# Enclosure_85x58_WS.net
KiCad netlist of a schematic drawn in EAGLE
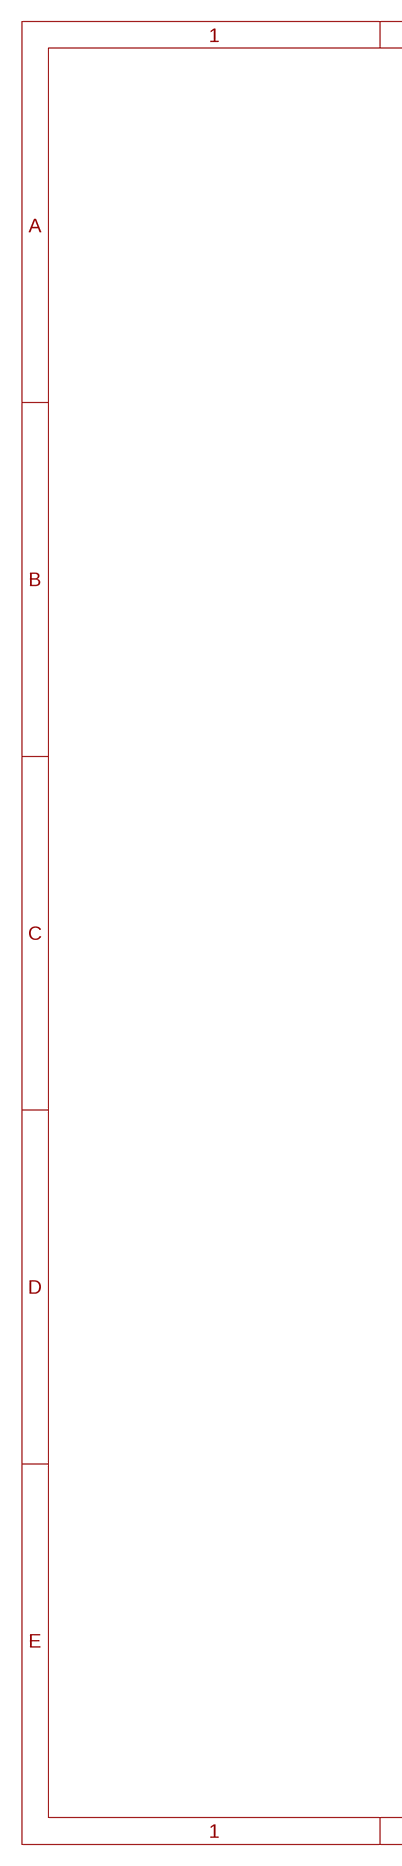
[diagram p0: schematic, sheet 1, part 1 of 2]
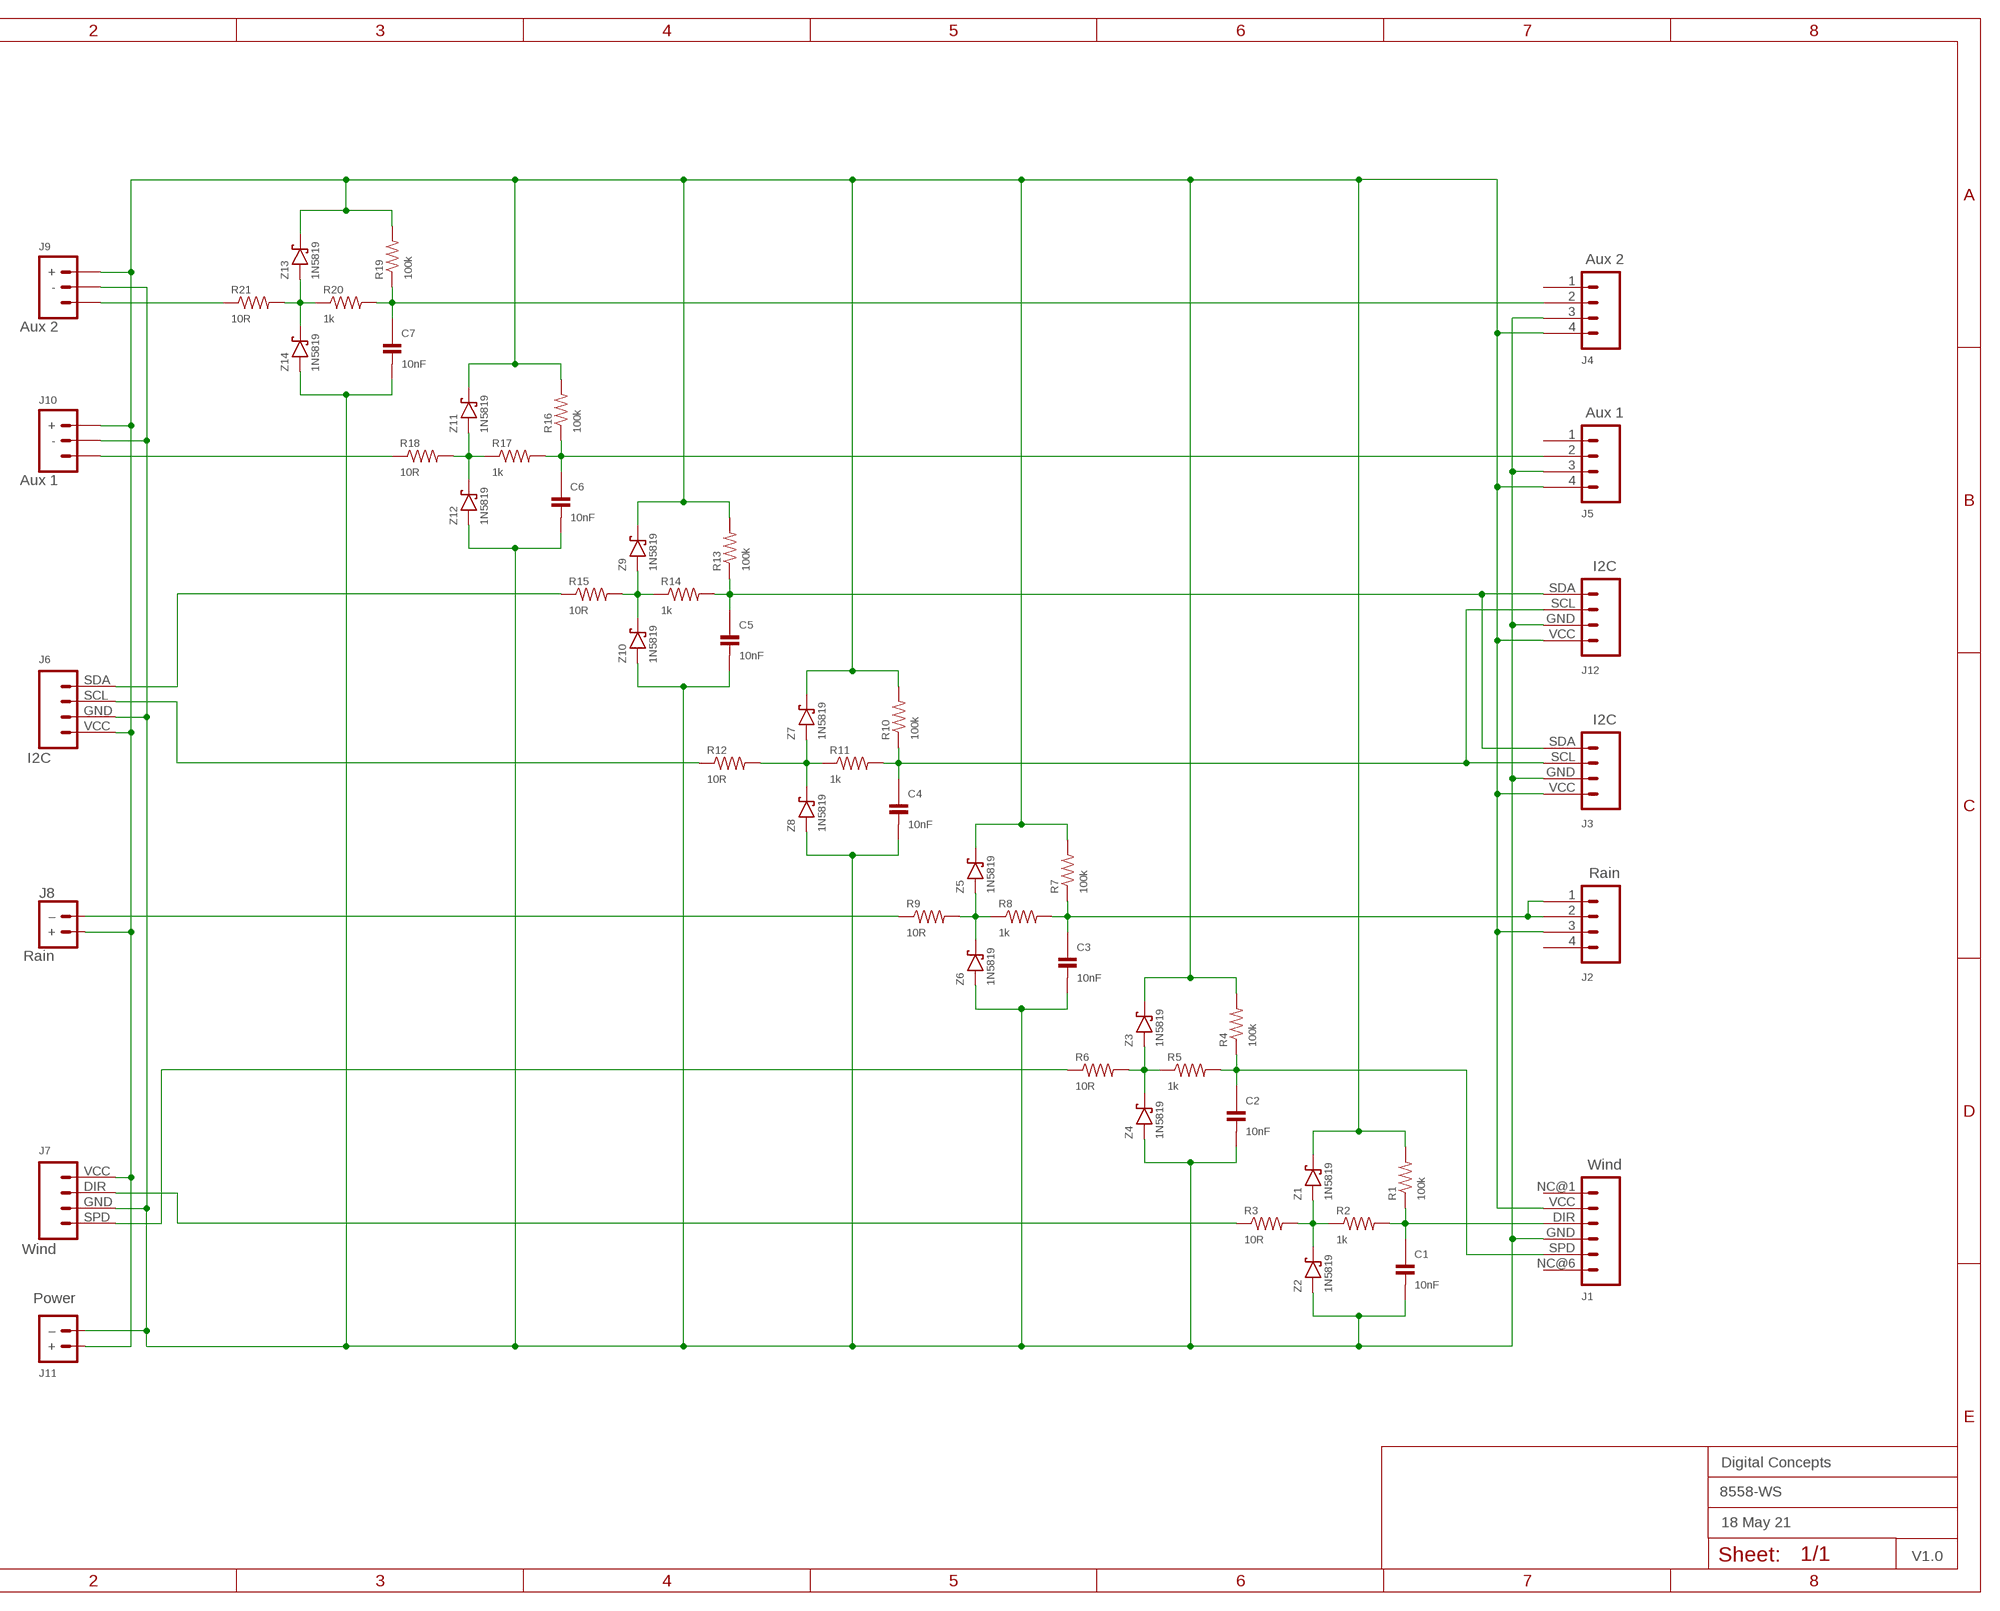
[diagram p1: schematic, sheet 1, part 2 of 2]

(export (version "E")
  (design (tool "Eeschema 10.0.6"))
  (components
    (comp (ref "C1")
      (value "10nF")
      (footprint "eagle-import:C0805-VIA-2")
      (libsource (lib "eagle-import") (part "CAPACITOR-0805-VIA-2"))
    )
    (comp (ref "C2")
      (value "10nF")
      (footprint "eagle-import:C0805-VIA-2")
      (libsource (lib "eagle-import") (part "CAPACITOR-0805-VIA-2"))
    )
    (comp (ref "C3")
      (value "10nF")
      (footprint "eagle-import:C0805-VIA-2")
      (libsource (lib "eagle-import") (part "CAPACITOR-0805-VIA-2"))
    )
    (comp (ref "C4")
      (value "10nF")
      (footprint "eagle-import:C0805-VIA-2")
      (libsource (lib "eagle-import") (part "CAPACITOR-0805-VIA-2"))
    )
    (comp (ref "C5")
      (value "10nF")
      (footprint "eagle-import:C0805-VIA-2")
      (libsource (lib "eagle-import") (part "CAPACITOR-0805-VIA-2"))
    )
    (comp (ref "C6")
      (value "10nF")
      (footprint "eagle-import:C0805-VIA-2")
      (libsource (lib "eagle-import") (part "CAPACITOR-0805-VIA-2"))
    )
    (comp (ref "C7")
      (value "10nF")
      (footprint "eagle-import:C0805-VIA-2")
      (libsource (lib "eagle-import") (part "CAPACITOR-0805-VIA-2"))
    )
    (comp (ref "J1")
      (value "Wind")
      (footprint "eagle-import:RJ11-6-VERTICAL-WIND")
      (libsource (lib "eagle-import") (part "RJ11-6P6C-VERTICAL-WIND"))
    )
    (comp (ref "J2")
      (value "Rain")
      (footprint "eagle-import:RJ11-4-VERTICAL")
      (libsource (lib "eagle-import") (part "RJ11-6P4C-VERTICAL"))
    )
    (comp (ref "J3")
      (value "I2C")
      (footprint "eagle-import:RJ11-4-VERTICAL-I2C")
      (libsource (lib "eagle-import") (part "RJ11-6P4C-VERTICAL-I2C"))
    )
    (comp (ref "J4")
      (value "Aux 2")
      (footprint "eagle-import:RJ11-4-VERTICAL")
      (libsource (lib "eagle-import") (part "RJ11-6P4C-VERTICAL"))
    )
    (comp (ref "J5")
      (value "Aux 1")
      (footprint "eagle-import:RJ11-4-VERTICAL")
      (libsource (lib "eagle-import") (part "RJ11-6P4C-VERTICAL"))
    )
    (comp (ref "J6")
      (value "I2C")
      (footprint "eagle-import:JST-PH2.0-4-VERTICAL-I2C")
      (libsource (lib "eagle-import") (part "JST-PH2.0-4-MALE-VERTICAL-I2C"))
    )
    (comp (ref "J7")
      (value "Wind")
      (footprint "eagle-import:JST-PH2.0-4-VERTICAL-WIND")
      (libsource (lib "eagle-import") (part "JST-PH2.0-4-MALE-VERTICAL-WIND"))
    )
    (comp (ref "J8")
      (value "Rain")
      (footprint "eagle-import:JST-PH2.0-2-VERTICAL=POWER")
      (libsource (lib "eagle-import") (part "JST-PH2.0-2-MALE-VERTICAL"))
    )
    (comp (ref "J9")
      (value "Aux 2")
      (footprint "eagle-import:JST-PH2.0-3-VERTICAL")
      (libsource (lib "eagle-import") (part "JST-PH2.0-3-MALE-VERTICAL"))
    )
    (comp (ref "J10")
      (value "Aux 1")
      (footprint "eagle-import:JST-PH2.0-3-VERTICAL")
      (libsource (lib "eagle-import") (part "JST-PH2.0-3-MALE-VERTICAL"))
    )
    (comp (ref "J11")
      (value "Power")
      (footprint "eagle-import:JST-PH2.0-2-VERTICAL=POWER")
      (libsource (lib "eagle-import") (part "JST-PH2.0-2-MALE-VERTICAL"))
    )
    (comp (ref "J12")
      (value "I2C")
      (footprint "eagle-import:CONN_04-I2C")
      (libsource (lib "eagle-import") (part "HEADER-1X4-I2C"))
    )
    (comp (ref "R1")
      (value "100k")
      (footprint "eagle-import:R0805")
      (libsource (lib "eagle-import") (part "RESISTORR0805"))
    )
    (comp (ref "R2")
      (value "1k")
      (footprint "eagle-import:R0805")
      (libsource (lib "eagle-import") (part "RESISTORR0805"))
    )
    (comp (ref "R3")
      (value "10R")
      (footprint "eagle-import:R0805-VIA-1")
      (libsource (lib "eagle-import") (part "RESISTOR-VIA-1"))
    )
    (comp (ref "R4")
      (value "100k")
      (footprint "eagle-import:R0805")
      (libsource (lib "eagle-import") (part "RESISTORR0805"))
    )
    (comp (ref "R5")
      (value "1k")
      (footprint "eagle-import:R0805")
      (libsource (lib "eagle-import") (part "RESISTORR0805"))
    )
    (comp (ref "R6")
      (value "10R")
      (footprint "eagle-import:R0805-VIA-1")
      (libsource (lib "eagle-import") (part "RESISTOR-VIA-1"))
    )
    (comp (ref "R7")
      (value "100k")
      (footprint "eagle-import:R0805")
      (libsource (lib "eagle-import") (part "RESISTORR0805"))
    )
    (comp (ref "R8")
      (value "1k")
      (footprint "eagle-import:R0805")
      (libsource (lib "eagle-import") (part "RESISTORR0805"))
    )
    (comp (ref "R9")
      (value "10R")
      (footprint "eagle-import:R0805-VIA-1")
      (libsource (lib "eagle-import") (part "RESISTOR-VIA-1"))
    )
    (comp (ref "R10")
      (value "100k")
      (footprint "eagle-import:R0805")
      (libsource (lib "eagle-import") (part "RESISTORR0805"))
    )
    (comp (ref "R11")
      (value "1k")
      (footprint "eagle-import:R0805")
      (libsource (lib "eagle-import") (part "RESISTORR0805"))
    )
    (comp (ref "R12")
      (value "10R")
      (footprint "eagle-import:R0805-VIA-1")
      (libsource (lib "eagle-import") (part "RESISTOR-VIA-1"))
    )
    (comp (ref "R13")
      (value "100k")
      (footprint "eagle-import:R0805")
      (libsource (lib "eagle-import") (part "RESISTORR0805"))
    )
    (comp (ref "R14")
      (value "1k")
      (footprint "eagle-import:R0805")
      (libsource (lib "eagle-import") (part "RESISTORR0805"))
    )
    (comp (ref "R15")
      (value "10R")
      (footprint "eagle-import:R0805-VIA-1")
      (libsource (lib "eagle-import") (part "RESISTOR-VIA-1"))
    )
    (comp (ref "R16")
      (value "100k")
      (footprint "eagle-import:R0805")
      (libsource (lib "eagle-import") (part "RESISTORR0805"))
    )
    (comp (ref "R17")
      (value "1k")
      (footprint "eagle-import:R0805")
      (libsource (lib "eagle-import") (part "RESISTORR0805"))
    )
    (comp (ref "R18")
      (value "10R")
      (footprint "eagle-import:R0805-VIA-1")
      (libsource (lib "eagle-import") (part "RESISTOR-VIA-1"))
    )
    (comp (ref "R19")
      (value "100k")
      (footprint "eagle-import:R0805")
      (libsource (lib "eagle-import") (part "RESISTORR0805"))
    )
    (comp (ref "R20")
      (value "1k")
      (footprint "eagle-import:R0805")
      (libsource (lib "eagle-import") (part "RESISTORR0805"))
    )
    (comp (ref "R21")
      (value "10R")
      (footprint "eagle-import:R0805-VIA-1")
      (libsource (lib "eagle-import") (part "RESISTOR-VIA-1"))
    )
    (comp (ref "Z1")
      (value "1N5819")
      (footprint "eagle-import:SOD-123")
      (libsource (lib "eagle-import") (part "DIODE-SCHOTTKY-1N5819"))
    )
    (comp (ref "Z2")
      (value "1N5819")
      (footprint "eagle-import:SOD-123-VIA-A")
      (libsource (lib "eagle-import") (part "DIODE-SCHOTTKY-1N5819-VIA-A"))
    )
    (comp (ref "Z3")
      (value "1N5819")
      (footprint "eagle-import:SOD-123")
      (libsource (lib "eagle-import") (part "DIODE-SCHOTTKY-1N5819"))
    )
    (comp (ref "Z4")
      (value "1N5819")
      (footprint "eagle-import:SOD-123-VIA-A")
      (libsource (lib "eagle-import") (part "DIODE-SCHOTTKY-1N5819-VIA-A"))
    )
    (comp (ref "Z5")
      (value "1N5819")
      (footprint "eagle-import:SOD-123")
      (libsource (lib "eagle-import") (part "DIODE-SCHOTTKY-1N5819"))
    )
    (comp (ref "Z6")
      (value "1N5819")
      (footprint "eagle-import:SOD-123-VIA-A")
      (libsource (lib "eagle-import") (part "DIODE-SCHOTTKY-1N5819-VIA-A"))
    )
    (comp (ref "Z7")
      (value "1N5819")
      (footprint "eagle-import:SOD-123")
      (libsource (lib "eagle-import") (part "DIODE-SCHOTTKY-1N5819"))
    )
    (comp (ref "Z8")
      (value "1N5819")
      (footprint "eagle-import:SOD-123-VIA-A")
      (libsource (lib "eagle-import") (part "DIODE-SCHOTTKY-1N5819-VIA-A"))
    )
    (comp (ref "Z9")
      (value "1N5819")
      (footprint "eagle-import:SOD-123")
      (libsource (lib "eagle-import") (part "DIODE-SCHOTTKY-1N5819"))
    )
    (comp (ref "Z10")
      (value "1N5819")
      (footprint "eagle-import:SOD-123-VIA-A")
      (libsource (lib "eagle-import") (part "DIODE-SCHOTTKY-1N5819-VIA-A"))
    )
    (comp (ref "Z11")
      (value "1N5819")
      (footprint "eagle-import:SOD-123")
      (libsource (lib "eagle-import") (part "DIODE-SCHOTTKY-1N5819"))
    )
    (comp (ref "Z12")
      (value "1N5819")
      (footprint "eagle-import:SOD-123-VIA-A")
      (libsource (lib "eagle-import") (part "DIODE-SCHOTTKY-1N5819-VIA-A"))
    )
    (comp (ref "Z13")
      (value "1N5819")
      (footprint "eagle-import:SOD-123")
      (libsource (lib "eagle-import") (part "DIODE-SCHOTTKY-1N5819"))
    )
    (comp (ref "Z14")
      (value "1N5819")
      (footprint "eagle-import:SOD-123-VIA-A")
      (libsource (lib "eagle-import") (part "DIODE-SCHOTTKY-1N5819-VIA-A"))
    )
  )
  (nets
    (net (code "1") (name "Net-(J1-2)") (class "Default")
      (node (ref "J1") (pin "VCC") (pinfunction "2_VCC") (pintype "passive"))
      (node (ref "J10") (pin "+") (pinfunction "+_+") (pintype "power_in"))
      (node (ref "J11") (pin "+") (pinfunction "+_+") (pintype "power_in"))
      (node (ref "J12") (pin "VCC") (pinfunction "1_VCC") (pintype "passive"))
      (node (ref "J2") (pin "3") (pinfunction "2_3") (pintype "passive"))
      (node (ref "J3") (pin "VCC") (pinfunction "1_VCC") (pintype "passive"))
      (node (ref "J4") (pin "4") (pinfunction "1_4") (pintype "passive"))
      (node (ref "J5") (pin "4") (pinfunction "1_4") (pintype "passive"))
      (node (ref "J6") (pin "VCC") (pinfunction "4_VCC") (pintype "passive"))
      (node (ref "J7") (pin "VCC") (pinfunction "1_VCC") (pintype "passive"))
      (node (ref "J8") (pin "+") (pinfunction "+_+") (pintype "power_in"))
      (node (ref "J9") (pin "+") (pinfunction "+_+") (pintype "power_in"))
      (node (ref "R1") (pin "2") (pinfunction "2_2") (pintype "passive"))
      (node (ref "R10") (pin "2") (pinfunction "2_2") (pintype "passive"))
      (node (ref "R13") (pin "2") (pinfunction "2_2") (pintype "passive"))
      (node (ref "R16") (pin "2") (pinfunction "2_2") (pintype "passive"))
      (node (ref "R19") (pin "2") (pinfunction "2_2") (pintype "passive"))
      (node (ref "R4") (pin "2") (pinfunction "2_2") (pintype "passive"))
      (node (ref "R7") (pin "2") (pinfunction "2_2") (pintype "passive"))
      (node (ref "Z1") (pin "C") (pinfunction "C_C") (pintype "passive"))
      (node (ref "Z11") (pin "C") (pinfunction "C_C") (pintype "passive"))
      (node (ref "Z13") (pin "C") (pinfunction "C_C") (pintype "passive"))
      (node (ref "Z3") (pin "C") (pinfunction "C_C") (pintype "passive"))
      (node (ref "Z5") (pin "C") (pinfunction "C_C") (pintype "passive"))
      (node (ref "Z7") (pin "C") (pinfunction "C_C") (pintype "passive"))
      (node (ref "Z9") (pin "C") (pinfunction "C_C") (pintype "passive"))
    )
    (net (code "2") (name "Net-(J1-3)") (class "Default")
      (node (ref "C1") (pin "1") (pinfunction "1_1") (pintype "passive"))
      (node (ref "J1") (pin "DIR") (pinfunction "3_DIR") (pintype "passive"))
      (node (ref "R1") (pin "1") (pinfunction "1_1") (pintype "passive"))
      (node (ref "R2") (pin "2") (pinfunction "2_2") (pintype "passive"))
    )
    (net (code "3") (name "Net-(J1-4)") (class "Default")
      (node (ref "C1") (pin "2") (pinfunction "2_2") (pintype "passive"))
      (node (ref "C1") (pin "2@VIA") (pinfunction "2_2@VIA") (pintype "passive"))
      (node (ref "C2") (pin "2") (pinfunction "2_2") (pintype "passive"))
      (node (ref "C2") (pin "2@VIA") (pinfunction "2_2@VIA") (pintype "passive"))
      (node (ref "C3") (pin "2") (pinfunction "2_2") (pintype "passive"))
      (node (ref "C3") (pin "2@VIA") (pinfunction "2_2@VIA") (pintype "passive"))
      (node (ref "C4") (pin "2") (pinfunction "2_2") (pintype "passive"))
      (node (ref "C4") (pin "2@VIA") (pinfunction "2_2@VIA") (pintype "passive"))
      (node (ref "C5") (pin "2") (pinfunction "2_2") (pintype "passive"))
      (node (ref "C5") (pin "2@VIA") (pinfunction "2_2@VIA") (pintype "passive"))
      (node (ref "C6") (pin "2") (pinfunction "2_2") (pintype "passive"))
      (node (ref "C6") (pin "2@VIA") (pinfunction "2_2@VIA") (pintype "passive"))
      (node (ref "C7") (pin "2") (pinfunction "2_2") (pintype "passive"))
      (node (ref "C7") (pin "2@VIA") (pinfunction "2_2@VIA") (pintype "passive"))
      (node (ref "J1") (pin "GND") (pinfunction "4_GND") (pintype "passive"))
      (node (ref "J10") (pin "-") (pinfunction "-_-") (pintype "power_in"))
      (node (ref "J11") (pin "-") (pinfunction "–_-") (pintype "power_in"))
      (node (ref "J12") (pin "GND") (pinfunction "2_GND") (pintype "passive"))
      (node (ref "J3") (pin "GND") (pinfunction "2_GND") (pintype "passive"))
      (node (ref "J4") (pin "3") (pinfunction "2_3") (pintype "passive"))
      (node (ref "J5") (pin "3") (pinfunction "2_3") (pintype "passive"))
      (node (ref "J6") (pin "GND") (pinfunction "3_GND") (pintype "passive"))
      (node (ref "J7") (pin "GND") (pinfunction "3_GND") (pintype "passive"))
      (node (ref "J9") (pin "-") (pinfunction "-_-") (pintype "power_in"))
      (node (ref "Z10") (pin "A") (pinfunction "A_A") (pintype "passive"))
      (node (ref "Z10") (pin "P$A") (pinfunction "A_P$A") (pintype "passive"))
      (node (ref "Z12") (pin "A") (pinfunction "A_A") (pintype "passive"))
      (node (ref "Z12") (pin "P$A") (pinfunction "A_P$A") (pintype "passive"))
      (node (ref "Z14") (pin "A") (pinfunction "A_A") (pintype "passive"))
      (node (ref "Z14") (pin "P$A") (pinfunction "A_P$A") (pintype "passive"))
      (node (ref "Z2") (pin "A") (pinfunction "A_A") (pintype "passive"))
      (node (ref "Z2") (pin "P$A") (pinfunction "A_P$A") (pintype "passive"))
      (node (ref "Z4") (pin "A") (pinfunction "A_A") (pintype "passive"))
      (node (ref "Z4") (pin "P$A") (pinfunction "A_P$A") (pintype "passive"))
      (node (ref "Z6") (pin "A") (pinfunction "A_A") (pintype "passive"))
      (node (ref "Z6") (pin "P$A") (pinfunction "A_P$A") (pintype "passive"))
      (node (ref "Z8") (pin "A") (pinfunction "A_A") (pintype "passive"))
      (node (ref "Z8") (pin "P$A") (pinfunction "A_P$A") (pintype "passive"))
    )
    (net (code "4") (name "Net-(J1-5)") (class "Default")
      (node (ref "C2") (pin "1") (pinfunction "1_1") (pintype "passive"))
      (node (ref "J1") (pin "SPD") (pinfunction "5_SPD") (pintype "passive"))
      (node (ref "R4") (pin "1") (pinfunction "1_1") (pintype "passive"))
      (node (ref "R5") (pin "2") (pinfunction "2_2") (pintype "passive"))
    )
    (net (code "5") (name "Net-(J2-3)") (class "Default")
      (node (ref "C3") (pin "1") (pinfunction "1_1") (pintype "passive"))
      (node (ref "J2") (pin "1") (pinfunction "4_1") (pintype "passive"))
      (node (ref "J2") (pin "2") (pinfunction "3_2") (pintype "passive"))
      (node (ref "R7") (pin "1") (pinfunction "1_1") (pintype "passive"))
      (node (ref "R8") (pin "2") (pinfunction "2_2") (pintype "passive"))
    )
    (net (code "6") (name "Net-(J4-3)") (class "Default")
      (node (ref "C7") (pin "1") (pinfunction "1_1") (pintype "passive"))
      (node (ref "J4") (pin "2") (pinfunction "3_2") (pintype "passive"))
      (node (ref "R19") (pin "1") (pinfunction "1_1") (pintype "passive"))
      (node (ref "R20") (pin "2") (pinfunction "2_2") (pintype "passive"))
    )
    (net (code "7") (name "Net-(J5-3)") (class "Default")
      (node (ref "C6") (pin "1") (pinfunction "1_1") (pintype "passive"))
      (node (ref "J5") (pin "2") (pinfunction "3_2") (pintype "passive"))
      (node (ref "R16") (pin "1") (pinfunction "1_1") (pintype "passive"))
      (node (ref "R17") (pin "2") (pinfunction "2_2") (pintype "passive"))
    )
    (net (code "8") (name "Net-(J6-1)") (class "Default")
      (node (ref "J6") (pin "SDA") (pinfunction "1_SDA") (pintype "passive"))
      (node (ref "R15") (pin "1") (pinfunction "1_1") (pintype "passive"))
      (node (ref "R15") (pin "1@VIA") (pinfunction "1_1@VIA") (pintype "passive"))
    )
    (net (code "9") (name "Net-(J6-2)") (class "Default")
      (node (ref "J6") (pin "SCL") (pinfunction "2_SCL") (pintype "passive"))
      (node (ref "R12") (pin "1") (pinfunction "1_1") (pintype "passive"))
      (node (ref "R12") (pin "1@VIA") (pinfunction "1_1@VIA") (pintype "passive"))
    )
    (net (code "10") (name "Net-(J7-2)") (class "Default")
      (node (ref "J7") (pin "DIR") (pinfunction "2_DIR") (pintype "passive"))
      (node (ref "R3") (pin "1") (pinfunction "1_1") (pintype "passive"))
      (node (ref "R3") (pin "1@VIA") (pinfunction "1_1@VIA") (pintype "passive"))
    )
    (net (code "11") (name "Net-(J7-4)") (class "Default")
      (node (ref "J7") (pin "SPD") (pinfunction "4_SPD") (pintype "passive"))
      (node (ref "R6") (pin "1") (pinfunction "1_1") (pintype "passive"))
      (node (ref "R6") (pin "1@VIA") (pinfunction "1_1@VIA") (pintype "passive"))
    )
    (net (code "12") (name "Net-(J8-–)") (class "Default")
      (node (ref "J8") (pin "-") (pinfunction "–_-") (pintype "power_in"))
      (node (ref "R9") (pin "1") (pinfunction "1_1") (pintype "passive"))
      (node (ref "R9") (pin "1@VIA") (pinfunction "1_1@VIA") (pintype "passive"))
    )
    (net (code "13") (name "Net-(J9-PadSIG)") (class "Default")
      (node (ref "J9") (pin "SIG") (pinfunction "SIG_SIG") (pintype "bidirectional"))
      (node (ref "R21") (pin "1") (pinfunction "1_1") (pintype "passive"))
      (node (ref "R21") (pin "1@VIA") (pinfunction "1_1@VIA") (pintype "passive"))
    )
    (net (code "14") (name "Net-(J10-PadSIG)") (class "Default")
      (node (ref "J10") (pin "SIG") (pinfunction "SIG_SIG") (pintype "bidirectional"))
      (node (ref "R18") (pin "1") (pinfunction "1_1") (pintype "passive"))
      (node (ref "R18") (pin "1@VIA") (pinfunction "1_1@VIA") (pintype "passive"))
    )
    (net (code "15") (name "Net-(J12-3)") (class "Default")
      (node (ref "C4") (pin "1") (pinfunction "1_1") (pintype "passive"))
      (node (ref "J12") (pin "SCL") (pinfunction "3_SCL") (pintype "passive"))
      (node (ref "J3") (pin "SCL") (pinfunction "3_SCL") (pintype "passive"))
      (node (ref "R10") (pin "1") (pinfunction "1_1") (pintype "passive"))
      (node (ref "R11") (pin "2") (pinfunction "2_2") (pintype "passive"))
    )
    (net (code "16") (name "Net-(J12-4)") (class "Default")
      (node (ref "C5") (pin "1") (pinfunction "1_1") (pintype "passive"))
      (node (ref "J12") (pin "SDA") (pinfunction "4_SDA") (pintype "passive"))
      (node (ref "J3") (pin "SDA") (pinfunction "4_SDA") (pintype "passive"))
      (node (ref "R13") (pin "1") (pinfunction "1_1") (pintype "passive"))
      (node (ref "R14") (pin "2") (pinfunction "2_2") (pintype "passive"))
    )
    (net (code "17") (name "Net-(R2-Pad1)") (class "Default")
      (node (ref "R2") (pin "1") (pinfunction "1_1") (pintype "passive"))
      (node (ref "R3") (pin "2") (pinfunction "2_2") (pintype "passive"))
      (node (ref "Z1") (pin "A") (pinfunction "A_A") (pintype "passive"))
      (node (ref "Z2") (pin "C") (pinfunction "C_C") (pintype "passive"))
    )
    (net (code "18") (name "Net-(R5-Pad1)") (class "Default")
      (node (ref "R5") (pin "1") (pinfunction "1_1") (pintype "passive"))
      (node (ref "R6") (pin "2") (pinfunction "2_2") (pintype "passive"))
      (node (ref "Z3") (pin "A") (pinfunction "A_A") (pintype "passive"))
      (node (ref "Z4") (pin "C") (pinfunction "C_C") (pintype "passive"))
    )
    (net (code "19") (name "Net-(R8-Pad1)") (class "Default")
      (node (ref "R8") (pin "1") (pinfunction "1_1") (pintype "passive"))
      (node (ref "R9") (pin "2") (pinfunction "2_2") (pintype "passive"))
      (node (ref "Z5") (pin "A") (pinfunction "A_A") (pintype "passive"))
      (node (ref "Z6") (pin "C") (pinfunction "C_C") (pintype "passive"))
    )
    (net (code "20") (name "Net-(R11-Pad1)") (class "Default")
      (node (ref "R11") (pin "1") (pinfunction "1_1") (pintype "passive"))
      (node (ref "R12") (pin "2") (pinfunction "2_2") (pintype "passive"))
      (node (ref "Z7") (pin "A") (pinfunction "A_A") (pintype "passive"))
      (node (ref "Z8") (pin "C") (pinfunction "C_C") (pintype "passive"))
    )
    (net (code "21") (name "Net-(R14-Pad1)") (class "Default")
      (node (ref "R14") (pin "1") (pinfunction "1_1") (pintype "passive"))
      (node (ref "R15") (pin "2") (pinfunction "2_2") (pintype "passive"))
      (node (ref "Z10") (pin "C") (pinfunction "C_C") (pintype "passive"))
      (node (ref "Z9") (pin "A") (pinfunction "A_A") (pintype "passive"))
    )
    (net (code "22") (name "Net-(R17-Pad1)") (class "Default")
      (node (ref "R17") (pin "1") (pinfunction "1_1") (pintype "passive"))
      (node (ref "R18") (pin "2") (pinfunction "2_2") (pintype "passive"))
      (node (ref "Z11") (pin "A") (pinfunction "A_A") (pintype "passive"))
      (node (ref "Z12") (pin "C") (pinfunction "C_C") (pintype "passive"))
    )
    (net (code "23") (name "Net-(R20-Pad1)") (class "Default")
      (node (ref "R20") (pin "1") (pinfunction "1_1") (pintype "passive"))
      (node (ref "R21") (pin "2") (pinfunction "2_2") (pintype "passive"))
      (node (ref "Z13") (pin "A") (pinfunction "A_A") (pintype "passive"))
      (node (ref "Z14") (pin "C") (pinfunction "C_C") (pintype "passive"))
    )
    (net (code "24") (name "unconnected-(J1-1-PadNC@1)") (class "Default")
      (node (ref "J1") (pin "NC@1") (pinfunction "1_NC@1") (pintype "passive"))
    )
    (net (code "25") (name "unconnected-(J1-6-PadNC@6)") (class "Default")
      (node (ref "J1") (pin "NC@6") (pinfunction "6_NC@6") (pintype "passive"))
    )
    (net (code "26") (name "unconnected-(J2-1-Pad4)") (class "Default")
      (node (ref "J2") (pin "4") (pinfunction "1_4") (pintype "passive"))
    )
    (net (code "27") (name "unconnected-(J4-4-Pad1)") (class "Default")
      (node (ref "J4") (pin "1") (pinfunction "4_1") (pintype "passive"))
    )
    (net (code "28") (name "unconnected-(J5-4-Pad1)") (class "Default")
      (node (ref "J5") (pin "1") (pinfunction "4_1") (pintype "passive"))
    )
  )
)
